# respirho675.net
KiCad netlist of a schematic drawn in EAGLE
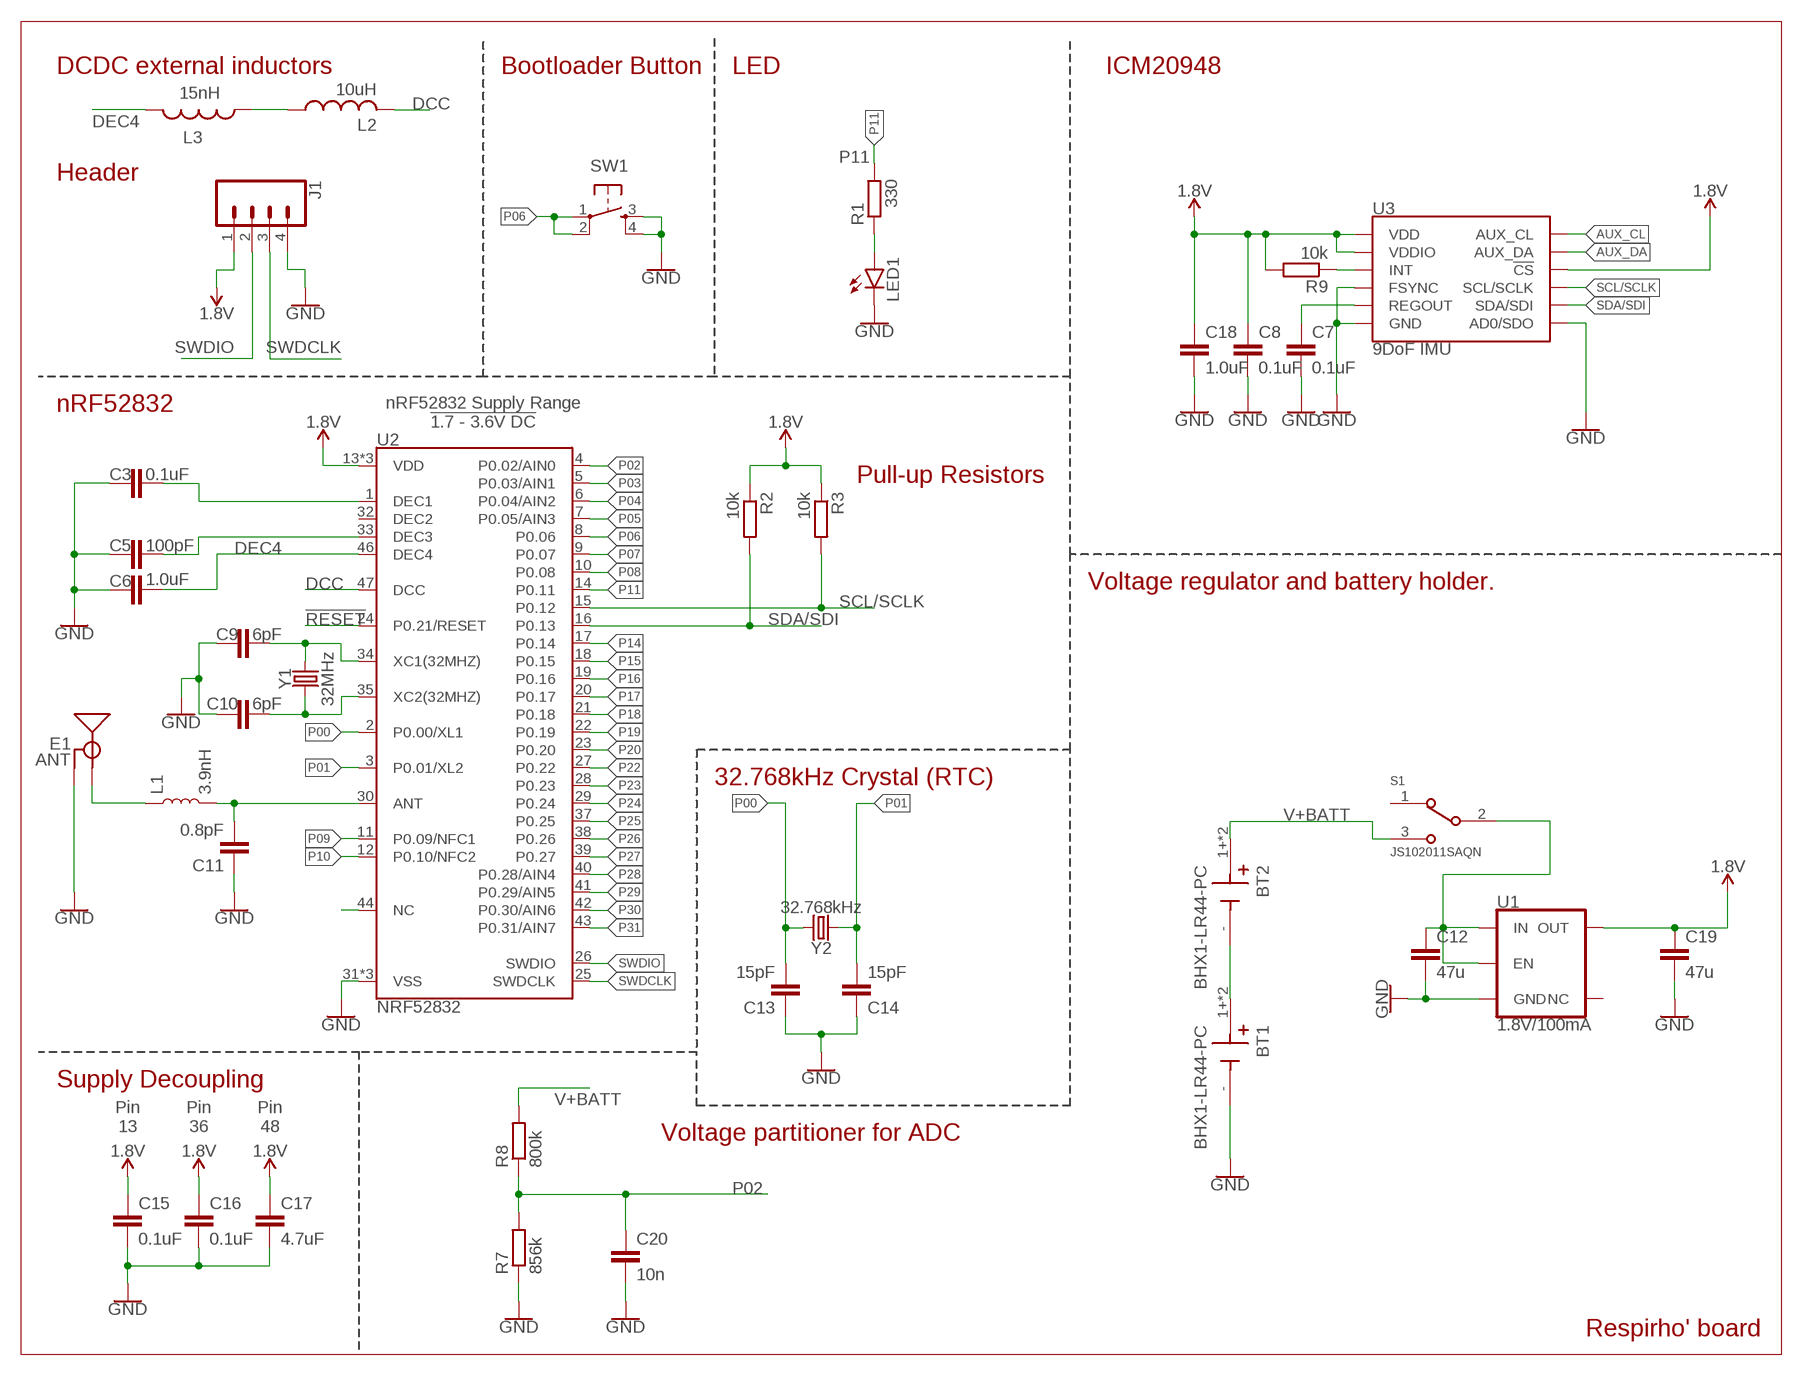
[diagram p0: schematic, sheet 1]

(export (version "E")
  (design (tool "Eeschema 10.0.6"))
  (components
    (comp (ref "BT1")
      (value "BHX1-LR44-PC")
      (footprint "eagle-import:BAT_BHX1-LR44-PC")
      (fields (field (name "DIGI-KEY_PART_NUMBER") "BHX1-LR44-PC-G-ND") (field (name "MF") "MPD"))
      (libsource (lib "eagle-import") (part "BHX1-LR44-PC"))
    )
    (comp (ref "BT2")
      (value "BHX1-LR44-PC")
      (footprint "eagle-import:BAT_BHX1-LR44-PC")
      (fields (field (name "DIGI-KEY_PART_NUMBER") "BHX1-LR44-PC-G-ND") (field (name "MF") "MPD"))
      (libsource (lib "eagle-import") (part "BHX1-LR44-PC"))
    )
    (comp (ref "C3")
      (value "0.1uF")
      (footprint "eagle-import:0402")
      (libsource (lib "eagle-import") (part "0.1UF-0402-16V-10%"))
    )
    (comp (ref "C5")
      (value "100pF")
      (footprint "eagle-import:0402")
      (libsource (lib "eagle-import") (part "100PF-0402-50V-5%"))
    )
    (comp (ref "C6")
      (value "1.0uF")
      (footprint "eagle-import:0402")
      (libsource (lib "eagle-import") (part "1.0UF-0402-16V-10%"))
    )
    (comp (ref "C7")
      (value "0.1uF")
      (footprint "eagle-import:0603")
      (libsource (lib "eagle-import") (part "0.1UF-0603-25V-5%"))
    )
    (comp (ref "C8")
      (value "0.1uF")
      (footprint "eagle-import:0603")
      (libsource (lib "eagle-import") (part "0.1UF-0603-25V-5%"))
    )
    (comp (ref "C9")
      (value "6pF")
      (footprint "eagle-import:0402")
      (libsource (lib "eagle-import") (part "6PF-0402-50V-0.5%"))
    )
    (comp (ref "C10")
      (value "6pF")
      (footprint "eagle-import:0402")
      (libsource (lib "eagle-import") (part "6PF-0402-50V-0.5%"))
    )
    (comp (ref "C11")
      (value "0.8pF")
      (footprint "eagle-import:0402")
      (libsource (lib "eagle-import") (part "0.8PF-0402-50V-0.1PF"))
    )
    (comp (ref "C12")
      (value "47u")
      (footprint "eagle-import:C0603")
      (libsource (lib "eagle-import") (part "C-EUC0603"))
    )
    (comp (ref "C13")
      (value "15pF")
      (footprint "eagle-import:0402")
      (libsource (lib "eagle-import") (part "15PF-0402-50V-5%"))
    )
    (comp (ref "C14")
      (value "15pF")
      (footprint "eagle-import:0402")
      (libsource (lib "eagle-import") (part "15PF-0402-50V-5%"))
    )
    (comp (ref "C15")
      (value "0.1uF")
      (footprint "eagle-import:0402")
      (libsource (lib "eagle-import") (part "0.1UF-0402-16V-10%"))
    )
    (comp (ref "C16")
      (value "0.1uF")
      (footprint "eagle-import:0402")
      (libsource (lib "eagle-import") (part "0.1UF-0402-16V-10%"))
    )
    (comp (ref "C17")
      (value "4.7uF")
      (footprint "eagle-import:0603")
      (libsource (lib "eagle-import") (part "4.7UF0603"))
    )
    (comp (ref "C18")
      (value "1.0uF")
      (footprint "eagle-import:0603")
      (libsource (lib "eagle-import") (part "1.0UF-0603-16V-10%-X7R"))
    )
    (comp (ref "C19")
      (value "47u")
      (footprint "eagle-import:C0603")
      (libsource (lib "eagle-import") (part "C-EUC0603"))
    )
    (comp (ref "C20")
      (value "10n")
      (footprint "eagle-import:C0603")
      (libsource (lib "eagle-import") (part "C-EUC0603"))
    )
    (comp (ref "E1")
      (value "ANT")
      (footprint "eagle-import:TRACE_ANTENNA_2.4GHZ_15.2MM")
      (libsource (lib "eagle-import") (part "ANTENNA-GROUNDEDTRACE-15.2MM"))
    )
    (comp (ref "J1")
      (value "CONN_04PTH")
      (footprint "eagle-import:1X04")
      (libsource (lib "eagle-import") (part "CONN_04PTH"))
    )
    (comp (ref "L1")
      (value "3.9nH")
      (footprint "eagle-import:0402")
      (libsource (lib "eagle-import") (part "INDUCTOR-0402-3.9NH"))
    )
    (comp (ref "L2")
      (value "10uH")
      (footprint "eagle-import:RESC0603_L")
      (libsource (lib "eagle-import") (part "INDUCTOR_0603_L"))
    )
    (comp (ref "L3")
      (value "15nH")
      (footprint "eagle-import:INDC1005X55N")
      (fields
        (field (name "DIGI-KEY_PART_NUMBER") "490-2625-1-ND")
        (field (name "MF") "Murata Electronics")
        (field (name "MP") "LQG15HS15NJ02D")
      )
      (libsource (lib "eagle-import") (part "LQG15HS15NJ02D"))
    )
    (comp (ref "LED1")
      (value "LEDCHIPLED_1206")
      (footprint "eagle-import:CHIPLED_1206")
      (libsource (lib "eagle-import") (part "LEDCHIPLED_1206"))
    )
    (comp (ref "R1")
      (value "330")
      (footprint "eagle-import:R0805")
      (libsource (lib "eagle-import") (part "R-EU_R0805"))
    )
    (comp (ref "R2")
      (value "10k")
      (footprint "eagle-import:R0603")
      (libsource (lib "eagle-import") (part "R-EU_R0603"))
    )
    (comp (ref "R3")
      (value "10k")
      (footprint "eagle-import:R0603")
      (libsource (lib "eagle-import") (part "R-EU_R0603"))
    )
    (comp (ref "R7")
      (value "856k")
      (footprint "eagle-import:R0603")
      (libsource (lib "eagle-import") (part "R-EU_R0603"))
    )
    (comp (ref "R8")
      (value "800k")
      (footprint "eagle-import:R0603")
      (libsource (lib "eagle-import") (part "R-EU_R0603"))
    )
    (comp (ref "R9")
      (value "10k")
      (footprint "eagle-import:R0603")
      (libsource (lib "eagle-import") (part "R-EU_R0603"))
    )
    (comp (ref "S1")
      (value "JS102011SAQN")
      (footprint "eagle-import:SW_JS102011SAQN")
      (fields (field (name "DIGI-KEY_PART_NUMBER") "401-1999-1-ND") (field (name "MF") "C&K"))
      (libsource (lib "eagle-import") (part "JS102011SAQN"))
    )
    (comp (ref "SW1")
      (value "SWITCH_SPST_4_PINRECT")
      (footprint "eagle-import:TACTILE_SWITCH_SMD_4.6X2.8MM")
      (libsource (lib "eagle-import") (part "SWITCH_SPST_4_PINRECT"))
    )
    (comp (ref "U1")
      (value "1.8V/100mA")
      (footprint "eagle-import:SC70")
      (libsource (lib "eagle-import") (part "V_REG_SP6214-1.8V"))
    )
    (comp (ref "U2")
      (value "NRF52832")
      (footprint "eagle-import:QFN48-6X6MM")
      (libsource (lib "eagle-import") (part "NRF52832"))
    )
    (comp (ref "U3")
      (value "9DoF IMU")
      (footprint "eagle-import:QFN24-3X3")
      (libsource (lib "eagle-import") (part "ICM-20948"))
    )
    (comp (ref "Y1")
      (value "32MHz")
      (footprint "eagle-import:CRYSTAL-SMD-2.0X1.6MM")
      (libsource (lib "eagle-import") (part "CRYSTAL-32MHZ-SMD-2.0X1.6MM"))
    )
    (comp (ref "Y2")
      (value "32.768kHz")
      (footprint "eagle-import:CRYSTAL-SMD-3.2X1.5MM")
      (libsource (lib "eagle-import") (part "CRYSTAL-32.768KHZSMD-3.2X1.5"))
    )
  )
  (nets
    (net (code "1") (name "/DCC") (class "Default")
      (node (ref "L2") (pin "2") (pinfunction "2_2") (pintype "passive"))
      (node (ref "U2") (pin "47") (pinfunction "DCC_47") (pintype "bidirectional"))
    )
    (net (code "2") (name "/DEC4") (class "Default")
      (node (ref "C6") (pin "2") (pinfunction "2_2") (pintype "passive"))
      (node (ref "L3") (pin "2") (pinfunction "2_2") (pintype "passive"))
      (node (ref "U2") (pin "46") (pinfunction "DEC4_46") (pintype "bidirectional"))
    )
    (net (code "3") (name "/V+BATT") (class "Default")
      (node (ref "BT2") (pin "1+") (pinfunction "+_1+") (pintype "passive"))
      (node (ref "BT2") (pin "2+") (pinfunction "+_2+") (pintype "passive"))
      (node (ref "R8") (pin "2") (pinfunction "2_2") (pintype "passive"))
      (node (ref "S1") (pin "3") (pinfunction "3_3") (pintype "passive"))
    )
    (net (code "4") (name "/~{RESET}") (class "Default")
      (node (ref "U2") (pin "24") (pinfunction "P0.21/RESET_24") (pintype "bidirectional"))
    )
    (net (code "5") (name "1.8V") (class "Default")
      (node (ref "C15") (pin "1") (pinfunction "1_1") (pintype "passive"))
      (node (ref "C16") (pin "1") (pinfunction "1_1") (pintype "passive"))
      (node (ref "C17") (pin "1") (pinfunction "1_1") (pintype "passive"))
      (node (ref "C18") (pin "1") (pinfunction "1_1") (pintype "passive"))
      (node (ref "C19") (pin "1") (pinfunction "1_1") (pintype "passive"))
      (node (ref "C8") (pin "1") (pinfunction "1_1") (pintype "passive"))
      (node (ref "J1") (pin "1") (pinfunction "1_1") (pintype "passive"))
      (node (ref "R2") (pin "1") (pinfunction "1_1") (pintype "passive"))
      (node (ref "R3") (pin "1") (pinfunction "1_1") (pintype "passive"))
      (node (ref "R9") (pin "2") (pinfunction "2_2") (pintype "passive"))
      (node (ref "U1") (pin "5") (pinfunction "OUT_5") (pintype "passive"))
      (node (ref "U2") (pin "13") (pinfunction "VDD_13") (pintype "bidirectional"))
      (node (ref "U2") (pin "36") (pinfunction "VDD_36") (pintype "bidirectional"))
      (node (ref "U2") (pin "48") (pinfunction "VDD_48") (pintype "bidirectional"))
      (node (ref "U3") (pin "13") (pinfunction "VDD_13") (pintype "bidirectional"))
      (node (ref "U3") (pin "22") (pinfunction "~{CS}_22") (pintype "bidirectional"))
      (node (ref "U3") (pin "8") (pinfunction "VDDIO_8") (pintype "bidirectional"))
    )
    (net (code "6") (name "AUX_CL") (class "Default")
      (node (ref "U3") (pin "7") (pinfunction "AUX_CL_7") (pintype "bidirectional"))
    )
    (net (code "7") (name "AUX_DA") (class "Default")
      (node (ref "U3") (pin "21") (pinfunction "AUX_DA_21") (pintype "bidirectional"))
    )
    (net (code "8") (name "GND") (class "Default")
      (node (ref "BT1") (pin "-") (pinfunction "-_-") (pintype "passive"))
      (node (ref "C10") (pin "2") (pinfunction "2_2") (pintype "passive"))
      (node (ref "C11") (pin "1") (pinfunction "1_1") (pintype "passive"))
      (node (ref "C12") (pin "2") (pinfunction "2_2") (pintype "passive"))
      (node (ref "C13") (pin "1") (pinfunction "1_1") (pintype "passive"))
      (node (ref "C14") (pin "1") (pinfunction "1_1") (pintype "passive"))
      (node (ref "C15") (pin "2") (pinfunction "2_2") (pintype "passive"))
      (node (ref "C16") (pin "2") (pinfunction "2_2") (pintype "passive"))
      (node (ref "C17") (pin "2") (pinfunction "2_2") (pintype "passive"))
      (node (ref "C18") (pin "2") (pinfunction "2_2") (pintype "passive"))
      (node (ref "C19") (pin "2") (pinfunction "2_2") (pintype "passive"))
      (node (ref "C20") (pin "2") (pinfunction "2_2") (pintype "passive"))
      (node (ref "C3") (pin "1") (pinfunction "1_1") (pintype "passive"))
      (node (ref "C5") (pin "1") (pinfunction "1_1") (pintype "passive"))
      (node (ref "C6") (pin "1") (pinfunction "1_1") (pintype "passive"))
      (node (ref "C7") (pin "2") (pinfunction "2_2") (pintype "passive"))
      (node (ref "C8") (pin "2") (pinfunction "2_2") (pintype "passive"))
      (node (ref "C9") (pin "1") (pinfunction "1_1") (pintype "passive"))
      (node (ref "E1") (pin "GND") (pinfunction "GND_GND") (pintype "bidirectional"))
      (node (ref "J1") (pin "4") (pinfunction "4_4") (pintype "passive"))
      (node (ref "LED1") (pin "C") (pinfunction "C_C") (pintype "passive"))
      (node (ref "R7") (pin "1") (pinfunction "1_1") (pintype "passive"))
      (node (ref "SW1") (pin "3") (pinfunction "3_3") (pintype "passive"))
      (node (ref "SW1") (pin "4") (pinfunction "4_4") (pintype "passive"))
      (node (ref "U1") (pin "2") (pinfunction "GND_2") (pintype "input"))
      (node (ref "U2") (pin "31") (pinfunction "VSS_31") (pintype "bidirectional"))
      (node (ref "U2") (pin "45") (pinfunction "VSS_45") (pintype "bidirectional"))
      (node (ref "U2") (pin "EP") (pinfunction "VSS_EP") (pintype "bidirectional"))
      (node (ref "U3") (pin "11") (pinfunction "FSYNC_11") (pintype "bidirectional"))
      (node (ref "U3") (pin "18") (pinfunction "GND_18") (pintype "bidirectional"))
      (node (ref "U3") (pin "20") (pinfunction "GND_20") (pintype "bidirectional"))
      (node (ref "U3") (pin "9") (pinfunction "AD0/SDO_9") (pintype "bidirectional"))
    )
    (net (code "9") (name "Net-(BT1-+-Pad1+)") (class "Default")
      (node (ref "BT1") (pin "1+") (pinfunction "+_1+") (pintype "passive"))
      (node (ref "BT1") (pin "2+") (pinfunction "+_2+") (pintype "passive"))
      (node (ref "BT2") (pin "-") (pinfunction "-_-") (pintype "passive"))
    )
    (net (code "10") (name "Net-(E1-SIGNAL)") (class "Default")
      (node (ref "E1") (pin "ANT") (pinfunction "SIGNAL_ANT") (pintype "bidirectional"))
      (node (ref "L1") (pin "1") (pinfunction "1_1") (pintype "passive"))
    )
    (net (code "11") (name "Net-(L2-Pad1)") (class "Default")
      (node (ref "L2") (pin "1") (pinfunction "1_1") (pintype "passive"))
      (node (ref "L3") (pin "1") (pinfunction "1_1") (pintype "passive"))
    )
    (net (code "12") (name "Net-(LED1-PadA)") (class "Default")
      (node (ref "LED1") (pin "A") (pinfunction "A_A") (pintype "passive"))
      (node (ref "R1") (pin "1") (pinfunction "1_1") (pintype "passive"))
    )
    (net (code "13") (name "Net-(U1-EN)") (class "Default")
      (node (ref "C12") (pin "1") (pinfunction "1_1") (pintype "passive"))
      (node (ref "S1") (pin "2") (pinfunction "2_2") (pintype "passive"))
      (node (ref "U1") (pin "1") (pinfunction "IN_1") (pintype "input"))
      (node (ref "U1") (pin "3") (pinfunction "EN_3") (pintype "input"))
    )
    (net (code "14") (name "Net-(U2-ANT)") (class "Default")
      (node (ref "C11") (pin "2") (pinfunction "2_2") (pintype "passive"))
      (node (ref "L1") (pin "2") (pinfunction "2_2") (pintype "passive"))
      (node (ref "U2") (pin "30") (pinfunction "ANT_30") (pintype "bidirectional"))
    )
    (net (code "15") (name "Net-(U2-DEC1)") (class "Default")
      (node (ref "C3") (pin "2") (pinfunction "2_2") (pintype "passive"))
      (node (ref "U2") (pin "1") (pinfunction "DEC1_1") (pintype "bidirectional"))
    )
    (net (code "16") (name "Net-(U2-DEC3)") (class "Default")
      (node (ref "C5") (pin "2") (pinfunction "2_2") (pintype "passive"))
      (node (ref "U2") (pin "33") (pinfunction "DEC3_33") (pintype "bidirectional"))
    )
    (net (code "17") (name "Net-(U2-XC1(32MHZ))") (class "Default")
      (node (ref "C9") (pin "2") (pinfunction "2_2") (pintype "passive"))
      (node (ref "U2") (pin "34") (pinfunction "XC1(32MHZ)_34") (pintype "bidirectional"))
      (node (ref "Y1") (pin "3") (pinfunction "2_3") (pintype "passive"))
    )
    (net (code "18") (name "Net-(U2-XC2(32MHZ))") (class "Default")
      (node (ref "C10") (pin "1") (pinfunction "1_1") (pintype "passive"))
      (node (ref "U2") (pin "35") (pinfunction "XC2(32MHZ)_35") (pintype "bidirectional"))
      (node (ref "Y1") (pin "1") (pinfunction "1_1") (pintype "passive"))
    )
    (net (code "19") (name "Net-(U3-INT)") (class "Default")
      (node (ref "R9") (pin "1") (pinfunction "1_1") (pintype "passive"))
      (node (ref "U3") (pin "12") (pinfunction "INT_12") (pintype "bidirectional"))
    )
    (net (code "20") (name "Net-(U3-REGOUT)") (class "Default")
      (node (ref "C7") (pin "1") (pinfunction "1_1") (pintype "passive"))
      (node (ref "U3") (pin "10") (pinfunction "REGOUT_10") (pintype "bidirectional"))
    )
    (net (code "21") (name "P00") (class "Default")
      (node (ref "C13") (pin "2") (pinfunction "2_2") (pintype "passive"))
      (node (ref "U2") (pin "2") (pinfunction "P0.00/XL1_2") (pintype "bidirectional"))
      (node (ref "Y2") (pin "P$2") (pinfunction "2_P$2") (pintype "passive"))
    )
    (net (code "22") (name "P01") (class "Default")
      (node (ref "C14") (pin "2") (pinfunction "2_2") (pintype "passive"))
      (node (ref "U2") (pin "3") (pinfunction "P0.01/XL2_3") (pintype "bidirectional"))
      (node (ref "Y2") (pin "P$1") (pinfunction "1_P$1") (pintype "passive"))
    )
    (net (code "23") (name "P02") (class "Default")
      (node (ref "C20") (pin "1") (pinfunction "1_1") (pintype "passive"))
      (node (ref "R7") (pin "2") (pinfunction "2_2") (pintype "passive"))
      (node (ref "R8") (pin "1") (pinfunction "1_1") (pintype "passive"))
      (node (ref "U2") (pin "4") (pinfunction "P0.02/AIN0_4") (pintype "bidirectional"))
    )
    (net (code "24") (name "P03") (class "Default")
      (node (ref "U2") (pin "5") (pinfunction "P0.03/AIN1_5") (pintype "bidirectional"))
    )
    (net (code "25") (name "P04") (class "Default")
      (node (ref "U2") (pin "6") (pinfunction "P0.04/AIN2_6") (pintype "bidirectional"))
    )
    (net (code "26") (name "P05") (class "Default")
      (node (ref "U2") (pin "7") (pinfunction "P0.05/AIN3_7") (pintype "bidirectional"))
    )
    (net (code "27") (name "P06") (class "Default")
      (node (ref "SW1") (pin "1") (pinfunction "1_1") (pintype "passive"))
      (node (ref "SW1") (pin "2") (pinfunction "2_2") (pintype "passive"))
      (node (ref "U2") (pin "8") (pinfunction "P0.06_8") (pintype "bidirectional"))
    )
    (net (code "28") (name "P07") (class "Default")
      (node (ref "U2") (pin "9") (pinfunction "P0.07_9") (pintype "bidirectional"))
    )
    (net (code "29") (name "P08") (class "Default")
      (node (ref "U2") (pin "10") (pinfunction "P0.08_10") (pintype "bidirectional"))
    )
    (net (code "30") (name "P09") (class "Default")
      (node (ref "U2") (pin "11") (pinfunction "P0.09/NFC1_11") (pintype "bidirectional"))
    )
    (net (code "31") (name "P10") (class "Default")
      (node (ref "U2") (pin "12") (pinfunction "P0.10/NFC2_12") (pintype "bidirectional"))
    )
    (net (code "32") (name "P11") (class "Default")
      (node (ref "R1") (pin "2") (pinfunction "2_2") (pintype "passive"))
      (node (ref "U2") (pin "14") (pinfunction "P0.11_14") (pintype "bidirectional"))
    )
    (net (code "33") (name "P14") (class "Default")
      (node (ref "U2") (pin "17") (pinfunction "P0.14_17") (pintype "bidirectional"))
    )
    (net (code "34") (name "P15") (class "Default")
      (node (ref "U2") (pin "18") (pinfunction "P0.15_18") (pintype "bidirectional"))
    )
    (net (code "35") (name "P16") (class "Default")
      (node (ref "U2") (pin "19") (pinfunction "P0.16_19") (pintype "bidirectional"))
    )
    (net (code "36") (name "P17") (class "Default")
      (node (ref "U2") (pin "20") (pinfunction "P0.17_20") (pintype "bidirectional"))
    )
    (net (code "37") (name "P18") (class "Default")
      (node (ref "U2") (pin "21") (pinfunction "P0.18_21") (pintype "bidirectional"))
    )
    (net (code "38") (name "P19") (class "Default")
      (node (ref "U2") (pin "22") (pinfunction "P0.19_22") (pintype "bidirectional"))
    )
    (net (code "39") (name "P20") (class "Default")
      (node (ref "U2") (pin "23") (pinfunction "P0.20_23") (pintype "bidirectional"))
    )
    (net (code "40") (name "P22") (class "Default")
      (node (ref "U2") (pin "27") (pinfunction "P0.22_27") (pintype "bidirectional"))
    )
    (net (code "41") (name "P23") (class "Default")
      (node (ref "U2") (pin "28") (pinfunction "P0.23_28") (pintype "bidirectional"))
    )
    (net (code "42") (name "P24") (class "Default")
      (node (ref "U2") (pin "29") (pinfunction "P0.24_29") (pintype "bidirectional"))
    )
    (net (code "43") (name "P25") (class "Default")
      (node (ref "U2") (pin "37") (pinfunction "P0.25_37") (pintype "bidirectional"))
    )
    (net (code "44") (name "P26") (class "Default")
      (node (ref "U2") (pin "38") (pinfunction "P0.26_38") (pintype "bidirectional"))
    )
    (net (code "45") (name "P27") (class "Default")
      (node (ref "U2") (pin "39") (pinfunction "P0.27_39") (pintype "bidirectional"))
    )
    (net (code "46") (name "P28") (class "Default")
      (node (ref "U2") (pin "40") (pinfunction "P0.28/AIN4_40") (pintype "bidirectional"))
    )
    (net (code "47") (name "P29") (class "Default")
      (node (ref "U2") (pin "41") (pinfunction "P0.29/AIN5_41") (pintype "bidirectional"))
    )
    (net (code "48") (name "P30") (class "Default")
      (node (ref "U2") (pin "42") (pinfunction "P0.30/AIN6_42") (pintype "bidirectional"))
    )
    (net (code "49") (name "P31") (class "Default")
      (node (ref "U2") (pin "43") (pinfunction "P0.31/AIN7_43") (pintype "bidirectional"))
    )
    (net (code "50") (name "SCL{slash}SCLK") (class "Default")
      (node (ref "R3") (pin "2") (pinfunction "2_2") (pintype "passive"))
      (node (ref "U2") (pin "15") (pinfunction "P0.12_15") (pintype "bidirectional"))
      (node (ref "U3") (pin "23") (pinfunction "SCL/SCLK_23") (pintype "bidirectional"))
    )
    (net (code "51") (name "SDA{slash}SDI") (class "Default")
      (node (ref "R2") (pin "2") (pinfunction "2_2") (pintype "passive"))
      (node (ref "U2") (pin "16") (pinfunction "P0.13_16") (pintype "bidirectional"))
      (node (ref "U3") (pin "24") (pinfunction "SDA/SDI_24") (pintype "bidirectional"))
    )
    (net (code "52") (name "SWDCLK") (class "Default")
      (node (ref "J1") (pin "3") (pinfunction "3_3") (pintype "passive"))
      (node (ref "U2") (pin "25") (pinfunction "SWDCLK_25") (pintype "bidirectional"))
    )
    (net (code "53") (name "SWDIO") (class "Default")
      (node (ref "J1") (pin "2") (pinfunction "2_2") (pintype "passive"))
      (node (ref "U2") (pin "26") (pinfunction "SWDIO_26") (pintype "bidirectional"))
    )
    (net (code "54") (name "unconnected-(S1-Pad1)") (class "Default")
      (node (ref "S1") (pin "1") (pinfunction "1_1") (pintype "passive"))
    )
    (net (code "55") (name "unconnected-(U1-NC-Pad4)") (class "Default")
      (node (ref "U1") (pin "4") (pinfunction "NC_4") (pintype "no_connect"))
    )
    (net (code "56") (name "unconnected-(U2-DEC2-Pad32)") (class "Default")
      (node (ref "U2") (pin "32") (pinfunction "DEC2_32") (pintype "bidirectional"))
    )
    (net (code "57") (name "unconnected-(U2-NC-Pad44)") (class "Default")
      (node (ref "U2") (pin "44") (pinfunction "NC_44") (pintype "bidirectional"))
    )
  )
)
